# DualETH_CON.net
KiCad netlist of a schematic drawn in Altium Designer
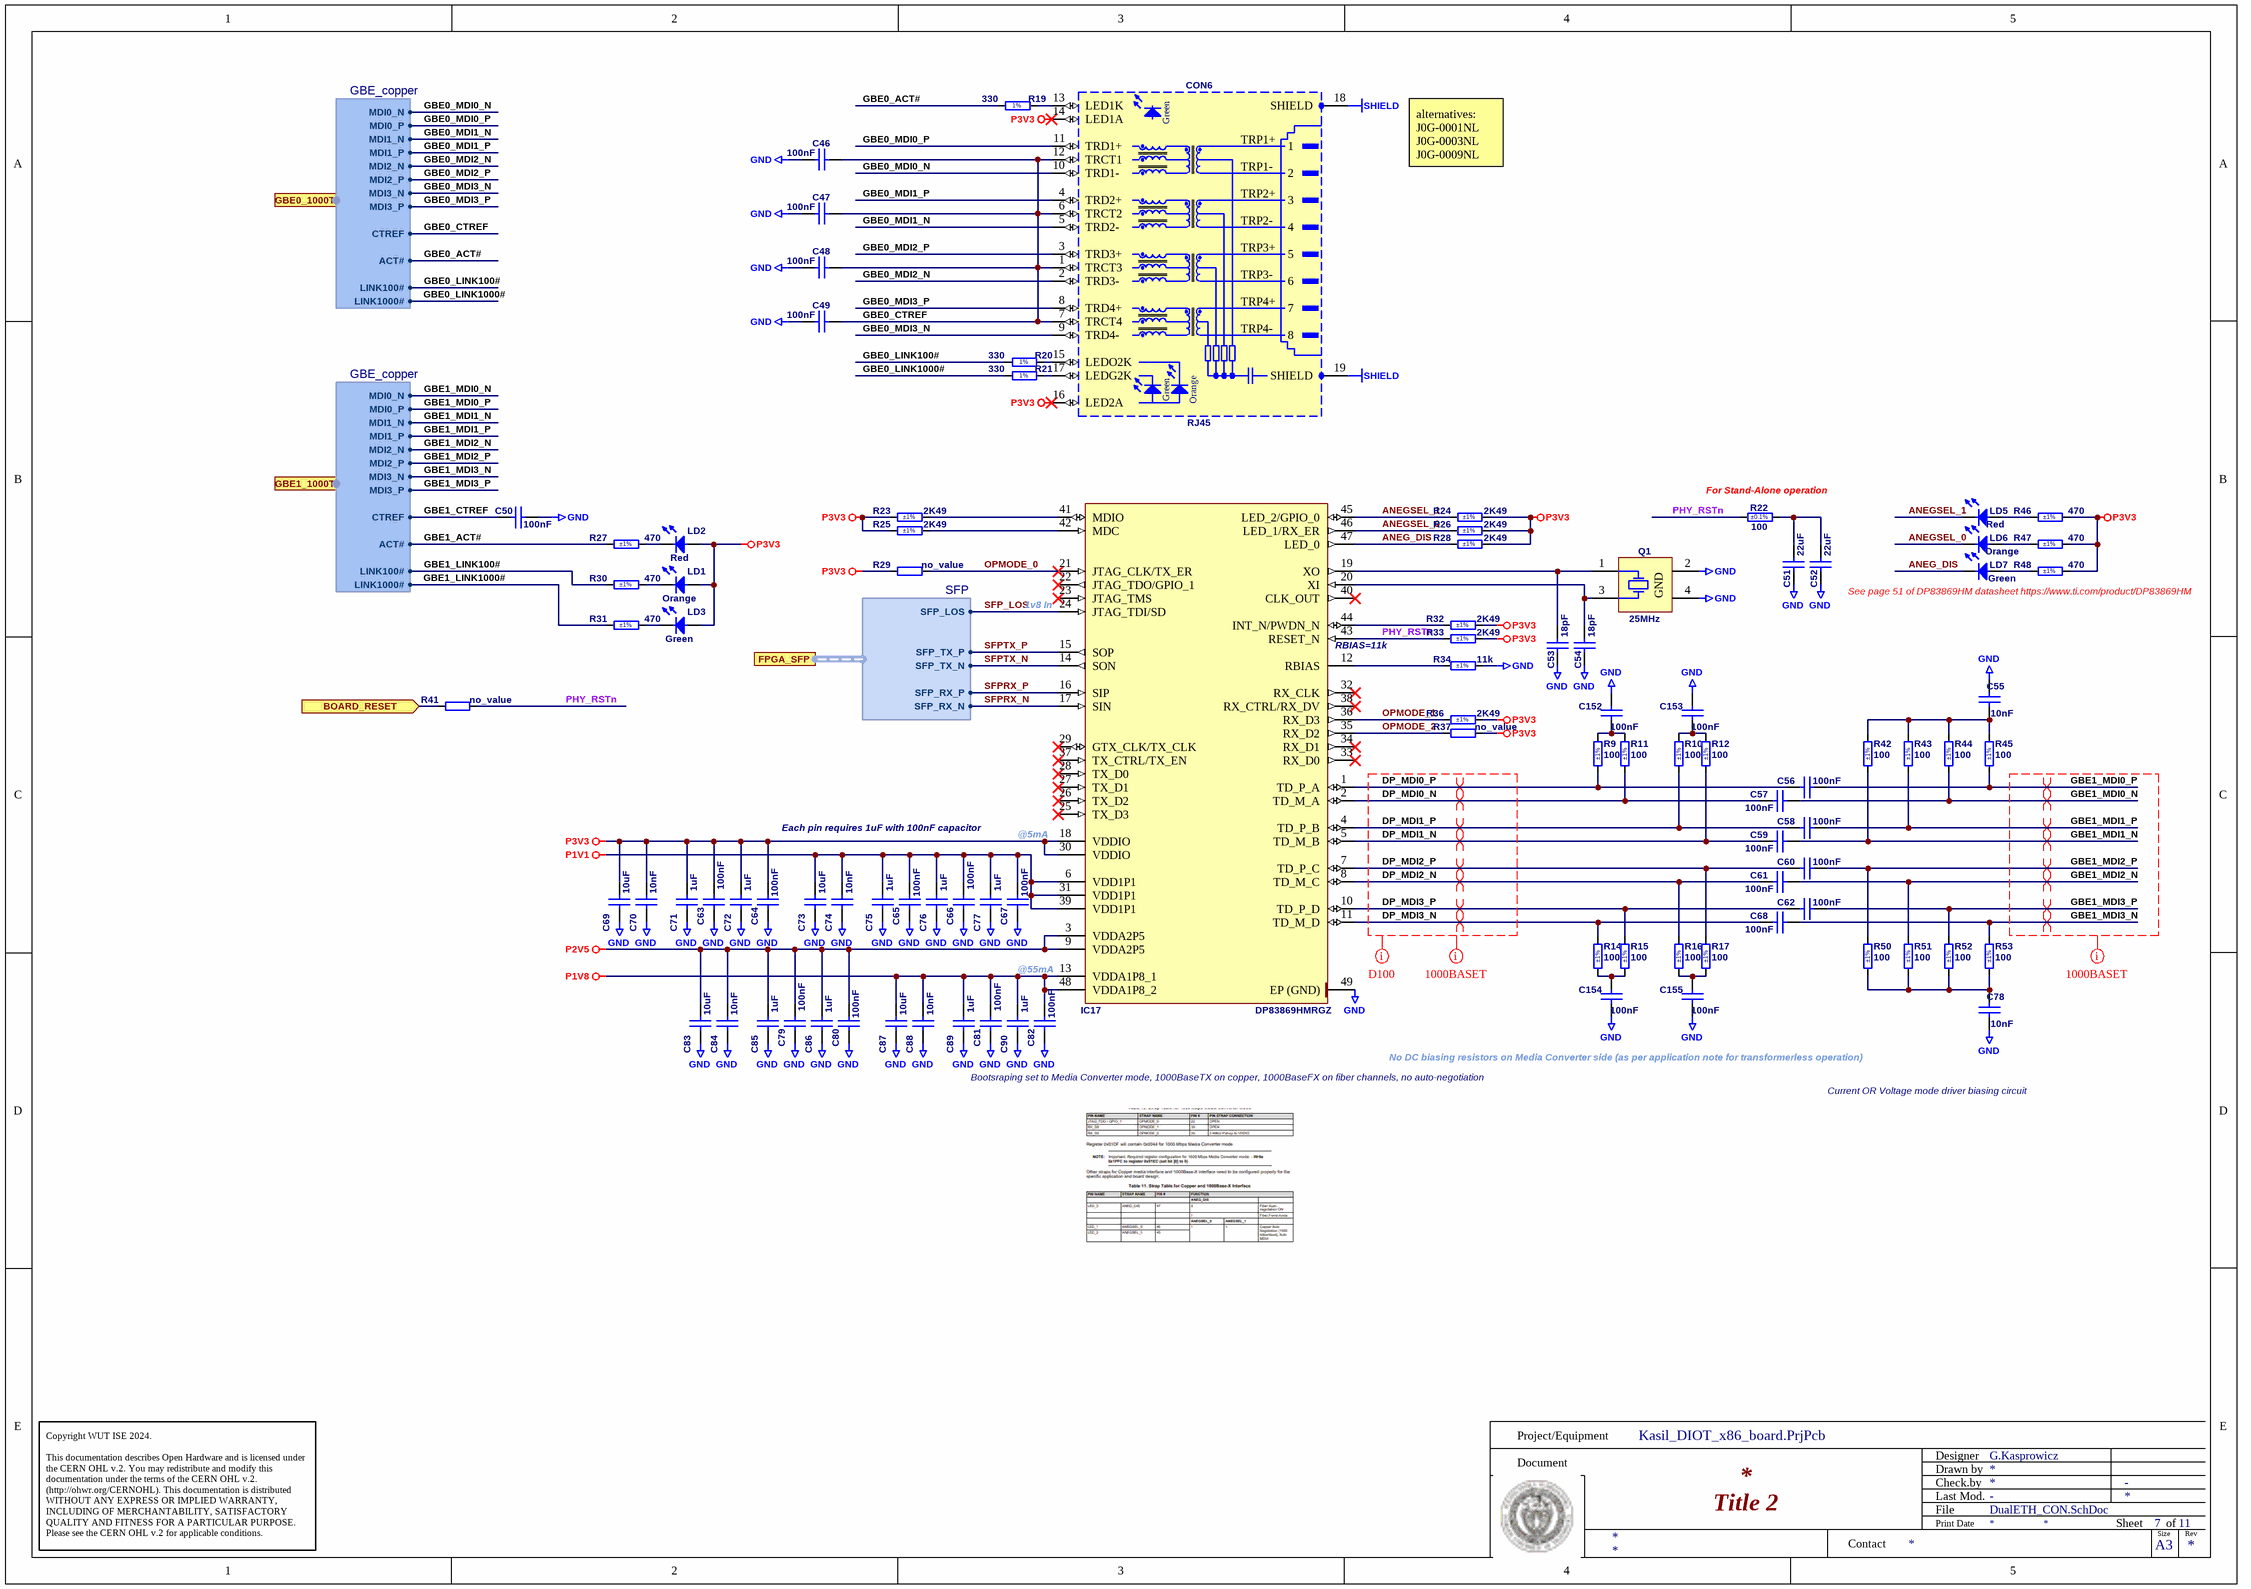
[diagram p0: DualETH_CON.SchDoc]

(export (version "E")
  (design (tool "Eeschema 10.0.6"))
  (components
    (comp (ref "C46")
      (value "100nF")
      (footprint "CAPC1005X55N")
      (description "Non-polarised capacitor")
      (fields (field (name "PART NUMBER") "CC0402_100NF_16V_10%_X7R") (field (name "VOLTAGE") "16V"))
      (libsource (lib "Capacitors") (part "Capacitor - non polarized"))
    )
    (comp (ref "C47")
      (value "100nF")
      (footprint "CAPC1005X55N")
      (description "Non-polarised capacitor")
      (fields (field (name "PART NUMBER") "CC0402_100NF_16V_10%_X7R") (field (name "VOLTAGE") "16V"))
      (libsource (lib "Capacitors") (part "Capacitor - non polarized"))
    )
    (comp (ref "C48")
      (value "100nF")
      (footprint "CAPC1005X55N")
      (description "Non-polarised capacitor")
      (fields (field (name "PART NUMBER") "CC0402_100NF_16V_10%_X7R") (field (name "VOLTAGE") "16V"))
      (libsource (lib "Capacitors") (part "Capacitor - non polarized"))
    )
    (comp (ref "C49")
      (value "100nF")
      (footprint "CAPC1005X55N")
      (description "Non-polarised capacitor")
      (fields (field (name "PART NUMBER") "CC0402_100NF_16V_10%_X7R") (field (name "VOLTAGE") "16V"))
      (libsource (lib "Capacitors") (part "Capacitor - non polarized"))
    )
    (comp (ref "C50")
      (value "100nF")
      (footprint "CAPC1005X55N")
      (description "Non-polarised capacitor")
      (fields (field (name "PART NUMBER") "CC0402_100NF_16V_10%_X7R") (field (name "VOLTAGE") "16V"))
      (libsource (lib "Capacitors") (part "Capacitor - non polarized"))
    )
    (comp (ref "C51")
      (value "22uF")
      (footprint "CAPC2012X135N")
      (description "Non-polarised capacitor")
      (fields
        (field (name "MANUFACTURER PART NUMBER") "CC0805_22UF_16V_10%_X5R")
        (field (name "MANUFACTURER") "GENERIC")
      )
      (libsource (lib "Capacitors") (part "Capacitor - non polarized"))
    )
    (comp (ref "C52")
      (value "22uF")
      (footprint "CAPC2012X135N")
      (description "Non-polarised capacitor")
      (fields
        (field (name "MANUFACTURER PART NUMBER") "CC0805_22UF_16V_10%_X5R")
        (field (name "MANUFACTURER") "GENERIC")
      )
      (libsource (lib "Capacitors") (part "Capacitor - non polarized"))
    )
    (comp (ref "C53")
      (value "18pF")
      (footprint "CAPC1005X55N")
      (description "Non-polarised capacitor")
      (fields (field (name "PART NUMBER") "CC0402_18PF_50V_5%_C0G") (field (name "VOLTAGE") "50V"))
      (libsource (lib "Capacitors") (part "Capacitor - non polarized"))
    )
    (comp (ref "C54")
      (value "18pF")
      (footprint "CAPC1005X55N")
      (description "Non-polarised capacitor")
      (fields (field (name "PART NUMBER") "CC0402_18PF_50V_5%_C0G") (field (name "VOLTAGE") "50V"))
      (libsource (lib "Capacitors") (part "Capacitor - non polarized"))
    )
    (comp (ref "C55")
      (value "10nF")
      (footprint "CAPC1005X55N")
      (description "Non-polarised capacitor")
      (fields (field (name "PART NUMBER") "CC0402_10NF_16V_10%_X7R") (field (name "VOLTAGE") "16V"))
      (libsource (lib "Capacitors") (part "Capacitor - non polarized"))
    )
    (comp (ref "C56")
      (value "100nF")
      (footprint "CAPC1005X55N")
      (description "Non-polarised capacitor")
      (fields (field (name "PART NUMBER") "CC0402_100NF_16V_10%_X7R") (field (name "VOLTAGE") "16V"))
      (libsource (lib "Capacitors") (part "Capacitor - non polarized"))
    )
    (comp (ref "C57")
      (value "100nF")
      (footprint "CAPC1005X55N")
      (description "Non-polarised capacitor")
      (fields (field (name "PART NUMBER") "CC0402_100NF_16V_10%_X7R") (field (name "VOLTAGE") "16V"))
      (libsource (lib "Capacitors") (part "Capacitor - non polarized"))
    )
    (comp (ref "C58")
      (value "100nF")
      (footprint "CAPC1005X55N")
      (description "Non-polarised capacitor")
      (fields (field (name "PART NUMBER") "CC0402_100NF_16V_10%_X7R") (field (name "VOLTAGE") "16V"))
      (libsource (lib "Capacitors") (part "Capacitor - non polarized"))
    )
    (comp (ref "C59")
      (value "100nF")
      (footprint "CAPC1005X55N")
      (description "Non-polarised capacitor")
      (fields (field (name "PART NUMBER") "CC0402_100NF_16V_10%_X7R") (field (name "VOLTAGE") "16V"))
      (libsource (lib "Capacitors") (part "Capacitor - non polarized"))
    )
    (comp (ref "C60")
      (value "100nF")
      (footprint "CAPC1005X55N")
      (description "Non-polarised capacitor")
      (fields (field (name "PART NUMBER") "CC0402_100NF_16V_10%_X7R") (field (name "VOLTAGE") "16V"))
      (libsource (lib "Capacitors") (part "Capacitor - non polarized"))
    )
    (comp (ref "C61")
      (value "100nF")
      (footprint "CAPC1005X55N")
      (description "Non-polarised capacitor")
      (fields (field (name "PART NUMBER") "CC0402_100NF_16V_10%_X7R") (field (name "VOLTAGE") "16V"))
      (libsource (lib "Capacitors") (part "Capacitor - non polarized"))
    )
    (comp (ref "C62")
      (value "100nF")
      (footprint "CAPC1005X55N")
      (description "Non-polarised capacitor")
      (fields (field (name "PART NUMBER") "CC0402_100NF_16V_10%_X7R") (field (name "VOLTAGE") "16V"))
      (libsource (lib "Capacitors") (part "Capacitor - non polarized"))
    )
    (comp (ref "C63")
      (value "100nF")
      (footprint "CAPC1005X55N")
      (description "Non-polarised capacitor")
      (fields (field (name "PART NUMBER") "CC0402_100NF_16V_10%_X7R") (field (name "VOLTAGE") "16V"))
      (libsource (lib "Capacitors") (part "Capacitor - non polarized"))
    )
    (comp (ref "C64")
      (value "100nF")
      (footprint "CAPC1005X55N")
      (description "Non-polarised capacitor")
      (fields (field (name "PART NUMBER") "CC0402_100NF_16V_10%_X7R") (field (name "VOLTAGE") "16V"))
      (libsource (lib "Capacitors") (part "Capacitor - non polarized"))
    )
    (comp (ref "C65")
      (value "100nF")
      (footprint "CAPC1005X55N")
      (description "Non-polarised capacitor")
      (fields (field (name "PART NUMBER") "CC0402_100NF_16V_10%_X7R") (field (name "VOLTAGE") "16V"))
      (libsource (lib "Capacitors") (part "Capacitor - non polarized"))
    )
    (comp (ref "C66")
      (value "100nF")
      (footprint "CAPC1005X55N")
      (description "Non-polarised capacitor")
      (fields (field (name "PART NUMBER") "CC0402_100NF_16V_10%_X7R") (field (name "VOLTAGE") "16V"))
      (libsource (lib "Capacitors") (part "Capacitor - non polarized"))
    )
    (comp (ref "C67")
      (value "100nF")
      (footprint "CAPC1005X55N")
      (description "Non-polarised capacitor")
      (fields (field (name "PART NUMBER") "CC0402_100NF_16V_10%_X7R") (field (name "VOLTAGE") "16V"))
      (libsource (lib "Capacitors") (part "Capacitor - non polarized"))
    )
    (comp (ref "C68")
      (value "100nF")
      (footprint "CAPC1005X55N")
      (description "Non-polarised capacitor")
      (fields (field (name "PART NUMBER") "CC0402_100NF_16V_10%_X7R") (field (name "VOLTAGE") "16V"))
      (libsource (lib "Capacitors") (part "Capacitor - non polarized"))
    )
    (comp (ref "C69")
      (value "10uF")
      (footprint "CAPC1608X80N")
      (description "Non-polarised capacitor")
      (fields (field (name "PART NUMBER") "CC0603_10UF_16V_20%_X5R") (field (name "VOLTAGE") "16V"))
      (libsource (lib "Capacitors") (part "Capacitor - non polarized"))
    )
    (comp (ref "C70")
      (value "10nF")
      (footprint "CAPC1005X55N")
      (description "Non-polarised capacitor")
      (fields (field (name "PART NUMBER") "CC0402_10NF_16V_10%_X7R") (field (name "VOLTAGE") "16V"))
      (libsource (lib "Capacitors") (part "Capacitor - non polarized"))
    )
    (comp (ref "C71")
      (value "1uF")
      (footprint "CAPC1005X55N")
      (description "Non-polarised capacitor")
      (fields (field (name "PART NUMBER") "CC0402_1UF_16V_10%_X5R") (field (name "VOLTAGE") "16V"))
      (libsource (lib "Capacitors") (part "Capacitor - non polarized"))
    )
    (comp (ref "C72")
      (value "1uF")
      (footprint "CAPC1005X55N")
      (description "Non-polarised capacitor")
      (fields (field (name "PART NUMBER") "CC0402_1UF_16V_10%_X5R") (field (name "VOLTAGE") "16V"))
      (libsource (lib "Capacitors") (part "Capacitor - non polarized"))
    )
    (comp (ref "C73")
      (value "10uF")
      (footprint "CAPC1608X80N")
      (description "Non-polarised capacitor")
      (fields (field (name "PART NUMBER") "CC0603_10UF_16V_20%_X5R") (field (name "VOLTAGE") "16V"))
      (libsource (lib "Capacitors") (part "Capacitor - non polarized"))
    )
    (comp (ref "C74")
      (value "10nF")
      (footprint "CAPC1005X55N")
      (description "Non-polarised capacitor")
      (fields (field (name "PART NUMBER") "CC0402_10NF_16V_10%_X7R") (field (name "VOLTAGE") "16V"))
      (libsource (lib "Capacitors") (part "Capacitor - non polarized"))
    )
    (comp (ref "C75")
      (value "1uF")
      (footprint "CAPC1005X55N")
      (description "Non-polarised capacitor")
      (fields (field (name "PART NUMBER") "CC0402_1UF_16V_10%_X5R") (field (name "VOLTAGE") "16V"))
      (libsource (lib "Capacitors") (part "Capacitor - non polarized"))
    )
    (comp (ref "C76")
      (value "1uF")
      (footprint "CAPC1005X55N")
      (description "Non-polarised capacitor")
      (fields (field (name "PART NUMBER") "CC0402_1UF_16V_10%_X5R") (field (name "VOLTAGE") "16V"))
      (libsource (lib "Capacitors") (part "Capacitor - non polarized"))
    )
    (comp (ref "C77")
      (value "1uF")
      (footprint "CAPC1005X55N")
      (description "Non-polarised capacitor")
      (fields (field (name "PART NUMBER") "CC0402_1UF_16V_10%_X5R") (field (name "VOLTAGE") "16V"))
      (libsource (lib "Capacitors") (part "Capacitor - non polarized"))
    )
    (comp (ref "C78")
      (value "10nF")
      (footprint "CAPC1005X55N")
      (description "Non-polarised capacitor")
      (fields (field (name "PART NUMBER") "CC0402_10NF_16V_10%_X7R") (field (name "VOLTAGE") "16V"))
      (libsource (lib "Capacitors") (part "Capacitor - non polarized"))
    )
    (comp (ref "C79")
      (value "100nF")
      (footprint "CAPC1005X55N")
      (description "Non-polarised capacitor")
      (fields (field (name "PART NUMBER") "CC0402_100NF_16V_10%_X7R") (field (name "VOLTAGE") "16V"))
      (libsource (lib "Capacitors") (part "Capacitor - non polarized"))
    )
    (comp (ref "C80")
      (value "100nF")
      (footprint "CAPC1005X55N")
      (description "Non-polarised capacitor")
      (fields (field (name "PART NUMBER") "CC0402_100NF_16V_10%_X7R") (field (name "VOLTAGE") "16V"))
      (libsource (lib "Capacitors") (part "Capacitor - non polarized"))
    )
    (comp (ref "C81")
      (value "100nF")
      (footprint "CAPC1005X55N")
      (description "Non-polarised capacitor")
      (fields (field (name "PART NUMBER") "CC0402_100NF_16V_10%_X7R") (field (name "VOLTAGE") "16V"))
      (libsource (lib "Capacitors") (part "Capacitor - non polarized"))
    )
    (comp (ref "C82")
      (value "100nF")
      (footprint "CAPC1005X55N")
      (description "Non-polarised capacitor")
      (fields (field (name "PART NUMBER") "CC0402_100NF_16V_10%_X7R") (field (name "VOLTAGE") "16V"))
      (libsource (lib "Capacitors") (part "Capacitor - non polarized"))
    )
    (comp (ref "C83")
      (value "10uF")
      (footprint "CAPC1608X80N")
      (description "Non-polarised capacitor")
      (fields (field (name "PART NUMBER") "CC0603_10UF_16V_20%_X5R") (field (name "VOLTAGE") "16V"))
      (libsource (lib "Capacitors") (part "Capacitor - non polarized"))
    )
    (comp (ref "C84")
      (value "10nF")
      (footprint "CAPC1005X55N")
      (description "Non-polarised capacitor")
      (fields (field (name "PART NUMBER") "CC0402_10NF_16V_10%_X7R") (field (name "VOLTAGE") "16V"))
      (libsource (lib "Capacitors") (part "Capacitor - non polarized"))
    )
    (comp (ref "C85")
      (value "1uF")
      (footprint "CAPC1005X55N")
      (description "Non-polarised capacitor")
      (fields (field (name "PART NUMBER") "CC0402_1UF_16V_10%_X5R") (field (name "VOLTAGE") "16V"))
      (libsource (lib "Capacitors") (part "Capacitor - non polarized"))
    )
    (comp (ref "C86")
      (value "1uF")
      (footprint "CAPC1005X55N")
      (description "Non-polarised capacitor")
      (fields (field (name "PART NUMBER") "CC0402_1UF_16V_10%_X5R") (field (name "VOLTAGE") "16V"))
      (libsource (lib "Capacitors") (part "Capacitor - non polarized"))
    )
    (comp (ref "C87")
      (value "10uF")
      (footprint "CAPC1608X80N")
      (description "Non-polarised capacitor")
      (fields (field (name "PART NUMBER") "CC0603_10UF_16V_20%_X5R") (field (name "VOLTAGE") "16V"))
      (libsource (lib "Capacitors") (part "Capacitor - non polarized"))
    )
    (comp (ref "C88")
      (value "10nF")
      (footprint "CAPC1005X55N")
      (description "Non-polarised capacitor")
      (fields (field (name "PART NUMBER") "CC0402_10NF_16V_10%_X7R") (field (name "VOLTAGE") "16V"))
      (libsource (lib "Capacitors") (part "Capacitor - non polarized"))
    )
    (comp (ref "C89")
      (value "1uF")
      (footprint "CAPC1005X55N")
      (description "Non-polarised capacitor")
      (fields (field (name "PART NUMBER") "CC0402_1UF_16V_10%_X5R") (field (name "VOLTAGE") "16V"))
      (libsource (lib "Capacitors") (part "Capacitor - non polarized"))
    )
    (comp (ref "C90")
      (value "1uF")
      (footprint "CAPC1005X55N")
      (description "Non-polarised capacitor")
      (fields (field (name "PART NUMBER") "CC0402_1UF_16V_10%_X5R") (field (name "VOLTAGE") "16V"))
      (libsource (lib "Capacitors") (part "Capacitor - non polarized"))
    )
    (comp (ref "C152")
      (value "100nF")
      (footprint "CAPC1005X55N")
      (description "Non-polarised capacitor")
      (fields (field (name "PART NUMBER") "CC0402_100NF_16V_10%_X7R") (field (name "VOLTAGE") "16V"))
      (libsource (lib "Capacitors") (part "Capacitor - non polarized"))
    )
    (comp (ref "C153")
      (value "100nF")
      (footprint "CAPC1005X55N")
      (description "Non-polarised capacitor")
      (fields (field (name "PART NUMBER") "CC0402_100NF_16V_10%_X7R") (field (name "VOLTAGE") "16V"))
      (libsource (lib "Capacitors") (part "Capacitor - non polarized"))
    )
    (comp (ref "C154")
      (value "100nF")
      (footprint "CAPC1005X55N")
      (description "Non-polarised capacitor")
      (fields (field (name "PART NUMBER") "CC0402_100NF_16V_10%_X7R") (field (name "VOLTAGE") "16V"))
      (libsource (lib "Capacitors") (part "Capacitor - non polarized"))
    )
    (comp (ref "C155")
      (value "100nF")
      (footprint "CAPC1005X55N")
      (description "Non-polarised capacitor")
      (fields (field (name "PART NUMBER") "CC0402_100NF_16V_10%_X7R") (field (name "VOLTAGE") "16V"))
      (libsource (lib "Capacitors") (part "Capacitor - non polarized"))
    )
    (comp (ref "CON6")
      (value "RJ45")
      (footprint "BELFUSE_L829-1J1T-43")
      (description "1 Port, RJ45, Gigabit Ethernet, MagJack Connector Module With Yellow And Green/Orange LEDs,")
      (fields (field (name "PART NUMBER") "BELFUSE_L829-1J1T-43") (field (name "MANUFACTURER") "BELFUSE"))
      (libsource (lib "Connectors") (part "BELFUSE_L829-1J1T-43"))
    )
    (comp (ref "IC17")
      (value "DP83869HMRGZ")
      (footprint "QFN50P700X700X100-49N-S420")
      (fields (field (name "MANUFACTURER") "TEXAS INSTRUMENTS"))
      (libsource (lib "ICs And Semiconductors") (part "DP83869HMRGZ"))
    )
    (comp (ref "LD1")
      (value "Orange")
      (footprint "LED_DIALIGHT_597-2111-407F")
      (fields
        (field (name "PART NUMBER") "LED_DIALIGHT_597-2111-407F")
        (field (name "MANUFACTURER") "DIALIGHT")
        (field (name "MANUFACTURER PART NUMBER") "597-2111-407F")
      )
      (libsource (lib "ICs And Semiconductors") (part "LED Red 1C 2A"))
    )
    (comp (ref "LD2")
      (value "Red")
      (footprint "LED_DIALIGHT_597-2111-407F")
      (fields
        (field (name "PART NUMBER") "LED_DIALIGHT_597-2111-407F")
        (field (name "MANUFACTURER") "DIALIGHT")
        (field (name "MANUFACTURER PART NUMBER") "597-2111-407F")
      )
      (libsource (lib "ICs And Semiconductors") (part "LED Red 1C 2A"))
    )
    (comp (ref "LD3")
      (value "Green")
      (footprint "LED_DIALIGHT_597-2111-407F")
      (fields
        (field (name "PART NUMBER") "LED_DIALIGHT_597-2111-407F")
        (field (name "MANUFACTURER") "DIALIGHT")
        (field (name "MANUFACTURER PART NUMBER") "597-2111-407F")
      )
      (libsource (lib "ICs And Semiconductors") (part "LED Red 1C 2A"))
    )
    (comp (ref "LD5")
      (value "Red")
      (footprint "LED_DIALIGHT_597-2111-407F")
      (fields
        (field (name "PART NUMBER") "LED_DIALIGHT_597-2111-407F")
        (field (name "MANUFACTURER") "DIALIGHT")
        (field (name "MANUFACTURER PART NUMBER") "597-2111-407F")
      )
      (libsource (lib "ICs And Semiconductors") (part "LED Red 1C 2A"))
    )
    (comp (ref "LD6")
      (value "Orange")
      (footprint "LED_DIALIGHT_597-2111-407F")
      (fields
        (field (name "PART NUMBER") "LED_DIALIGHT_597-2111-407F")
        (field (name "MANUFACTURER") "DIALIGHT")
        (field (name "MANUFACTURER PART NUMBER") "597-2111-407F")
      )
      (libsource (lib "ICs And Semiconductors") (part "LED Red 1C 2A"))
    )
    (comp (ref "LD7")
      (value "Green")
      (footprint "LED_DIALIGHT_597-2111-407F")
      (fields
        (field (name "PART NUMBER") "LED_DIALIGHT_597-2111-407F")
        (field (name "MANUFACTURER") "DIALIGHT")
        (field (name "MANUFACTURER PART NUMBER") "597-2111-407F")
      )
      (libsource (lib "ICs And Semiconductors") (part "LED Red 1C 2A"))
    )
    (comp (ref "Q1")
      (value "25MHz")
      (footprint "XTAL_EPSON_TSX-3225")
      (description "Crystal 4 pins 1=XTAL Control 2=GND3=XTAL 4=GND")
      (fields
        (field (name "PART NUMBER") "XTAL_25MHZ_EPSON_TSX-3225 25.0000MF10Z-AC")
        (field (name "MANUFACTURER") "EPSON")
      )
      (libsource (lib "ICs And Semiconductors") (part "Quartz Crystal 1X 2GND 3X 4GND"))
    )
    (comp (ref "R9")
      (value "100")
      (footprint "RESC1005X40N")
      (description "Resistor - 1%")
      (fields
        (field (name "TOLERANCE") "±1%")
        (field (name "PART NUMBER") "R0402_100R_1%_0.0625W_100PPM")
        (field (name "POWER") "0.0625W")
      )
      (libsource (lib "Resistors") (part "Resistor - 1%"))
    )
    (comp (ref "R10")
      (value "100")
      (footprint "RESC1005X40N")
      (description "Resistor - 1%")
      (fields
        (field (name "TOLERANCE") "±1%")
        (field (name "PART NUMBER") "R0402_100R_1%_0.0625W_100PPM")
        (field (name "POWER") "0.0625W")
      )
      (libsource (lib "Resistors") (part "Resistor - 1%"))
    )
    (comp (ref "R11")
      (value "100")
      (footprint "RESC1005X40N")
      (description "Resistor - 1%")
      (fields
        (field (name "TOLERANCE") "±1%")
        (field (name "PART NUMBER") "R0402_100R_1%_0.0625W_100PPM")
        (field (name "POWER") "0.0625W")
      )
      (libsource (lib "Resistors") (part "Resistor - 1%"))
    )
    (comp (ref "R12")
      (value "100")
      (footprint "RESC1005X40N")
      (description "Resistor - 1%")
      (fields
        (field (name "TOLERANCE") "±1%")
        (field (name "PART NUMBER") "R0402_100R_1%_0.0625W_100PPM")
        (field (name "POWER") "0.0625W")
      )
      (libsource (lib "Resistors") (part "Resistor - 1%"))
    )
    (comp (ref "R14")
      (value "100")
      (footprint "RESC1005X40N")
      (description "Resistor - 1%")
      (fields
        (field (name "TOLERANCE") "±1%")
        (field (name "PART NUMBER") "R0402_100R_1%_0.0625W_100PPM")
        (field (name "POWER") "0.0625W")
      )
      (libsource (lib "Resistors") (part "Resistor - 1%"))
    )
    (comp (ref "R15")
      (value "100")
      (footprint "RESC1005X40N")
      (description "Resistor - 1%")
      (fields
        (field (name "TOLERANCE") "±1%")
        (field (name "PART NUMBER") "R0402_100R_1%_0.0625W_100PPM")
        (field (name "POWER") "0.0625W")
      )
      (libsource (lib "Resistors") (part "Resistor - 1%"))
    )
    (comp (ref "R16")
      (value "100")
      (footprint "RESC1005X40N")
      (description "Resistor - 1%")
      (fields
        (field (name "TOLERANCE") "±1%")
        (field (name "PART NUMBER") "R0402_100R_1%_0.0625W_100PPM")
        (field (name "POWER") "0.0625W")
      )
      (libsource (lib "Resistors") (part "Resistor - 1%"))
    )
    (comp (ref "R17")
      (value "100")
      (footprint "RESC1005X40N")
      (description "Resistor - 1%")
      (fields
        (field (name "TOLERANCE") "±1%")
        (field (name "PART NUMBER") "R0402_100R_1%_0.0625W_100PPM")
        (field (name "POWER") "0.0625W")
      )
      (libsource (lib "Resistors") (part "Resistor - 1%"))
    )
    (comp (ref "R19")
      (value "330")
      (footprint "RESC1608X55N")
      (description "Resistor - 1%")
      (fields (field (name "PART NUMBER") "R0603_330R_1%_0.1W_100PPM") (field (name "POWER") "0.1W"))
      (libsource (lib "") (part "Resistor - 1%_1"))
    )
    (comp (ref "R20")
      (value "330")
      (footprint "RESC1608X55N")
      (description "Resistor - 1%")
      (fields (field (name "PART NUMBER") "R0603_330R_1%_0.1W_100PPM") (field (name "POWER") "0.1W"))
      (libsource (lib "") (part "Resistor - 1%_1"))
    )
    (comp (ref "R21")
      (value "330")
      (footprint "RESC1608X55N")
      (description "Resistor - 1%")
      (fields (field (name "PART NUMBER") "R0603_330R_1%_0.1W_100PPM") (field (name "POWER") "0.1W"))
      (libsource (lib "") (part "Resistor - 1%_1"))
    )
    (comp (ref "R22")
      (value "100")
      (footprint "RESC1005X35N")
      (description "Resistor - 0.1%")
      (fields
        (field (name "TOLERANCE") "±0.1%")
        (field (name "PART NUMBER") "R0402_100R_0.1%_0.063W_25PPM")
        (field (name "POWER") "0.063W")
      )
      (libsource (lib "Resistors") (part "Resistor - 0.1%"))
    )
    (comp (ref "R23")
      (value "2K49")
      (footprint "RESC1005X40N")
      (description "Resistor - 1%")
      (fields
        (field (name "TOLERANCE") "±1%")
        (field (name "PART NUMBER") "R0402_2K49_1%_0.063W_100PPM")
        (field (name "POWER") "0.063W")
      )
      (libsource (lib "Resistors") (part "Resistor - 1%"))
    )
    (comp (ref "R24")
      (value "2K49")
      (footprint "RESC1005X40N")
      (description "Resistor - 1%")
      (fields
        (field (name "TOLERANCE") "±1%")
        (field (name "PART NUMBER") "R0402_2K49_1%_0.063W_100PPM")
        (field (name "POWER") "0.063W")
      )
      (libsource (lib "Resistors") (part "Resistor - 1%"))
    )
    (comp (ref "R25")
      (value "2K49")
      (footprint "RESC1005X40N")
      (description "Resistor - 1%")
      (fields
        (field (name "TOLERANCE") "±1%")
        (field (name "PART NUMBER") "R0402_2K49_1%_0.063W_100PPM")
        (field (name "POWER") "0.063W")
      )
      (libsource (lib "Resistors") (part "Resistor - 1%"))
    )
    (comp (ref "R26")
      (value "2K49")
      (footprint "RESC1005X40N")
      (description "Resistor - 1%")
      (fields
        (field (name "TOLERANCE") "±1%")
        (field (name "PART NUMBER") "R0402_2K49_1%_0.063W_100PPM")
        (field (name "POWER") "0.063W")
      )
      (libsource (lib "Resistors") (part "Resistor - 1%"))
    )
    (comp (ref "R27")
      (value "470")
      (footprint "RESC1005X40N")
      (description "Resistor - 1%")
      (fields
        (field (name "TOLERANCE") "±1%")
        (field (name "PART NUMBER") "R0402_470R_1%_0.0625W_100PPM")
        (field (name "POWER") "0.0625W")
      )
      (libsource (lib "Resistors") (part "Resistor - 1%"))
    )
    (comp (ref "R28")
      (value "2K49")
      (footprint "RESC1005X40N")
      (description "Resistor - 1%")
      (fields
        (field (name "TOLERANCE") "±1%")
        (field (name "PART NUMBER") "R0402_2K49_1%_0.063W_100PPM")
        (field (name "POWER") "0.063W")
      )
      (libsource (lib "Resistors") (part "Resistor - 1%"))
    )
    (comp (ref "R29")
      (value "no_value")
      (footprint "RESC1005X40N")
      (description "Resistor")
      (fields (field (name "PART NUMBER") "R0402_0R_JUMPER") (field (name "MANUFACTURER") "GENERIC"))
      (libsource (lib "Resistors") (part "Resistor"))
    )
    (comp (ref "R30")
      (value "470")
      (footprint "RESC1005X40N")
      (description "Resistor - 1%")
      (fields
        (field (name "TOLERANCE") "±1%")
        (field (name "PART NUMBER") "R0402_470R_1%_0.0625W_100PPM")
        (field (name "POWER") "0.0625W")
      )
      (libsource (lib "Resistors") (part "Resistor - 1%"))
    )
    (comp (ref "R31")
      (value "470")
      (footprint "RESC1005X40N")
      (description "Resistor - 1%")
      (fields
        (field (name "TOLERANCE") "±1%")
        (field (name "PART NUMBER") "R0402_470R_1%_0.0625W_100PPM")
        (field (name "POWER") "0.0625W")
      )
      (libsource (lib "Resistors") (part "Resistor - 1%"))
    )
    (comp (ref "R32")
      (value "2K49")
      (footprint "RESC1005X40N")
      (description "Resistor - 1%")
      (fields
        (field (name "TOLERANCE") "±1%")
        (field (name "PART NUMBER") "R0402_2K49_1%_0.063W_100PPM")
        (field (name "POWER") "0.063W")
      )
      (libsource (lib "Resistors") (part "Resistor - 1%"))
    )
    (comp (ref "R33")
      (value "2K49")
      (footprint "RESC1005X40N")
      (description "Resistor - 1%")
      (fields
        (field (name "TOLERANCE") "±1%")
        (field (name "PART NUMBER") "R0402_2K49_1%_0.063W_100PPM")
        (field (name "POWER") "0.063W")
      )
      (libsource (lib "Resistors") (part "Resistor - 1%"))
    )
    (comp (ref "R34")
      (value "11k")
      (footprint "RESC1005X40N")
      (description "Resistor - 1%")
      (fields
        (field (name "TOLERANCE") "±1%")
        (field (name "PART NUMBER") "R0402_11K_1%_0.0625W_100PPM")
        (field (name "POWER") "0.0625W")
      )
      (libsource (lib "Resistors") (part "Resistor - 1%"))
    )
    (comp (ref "R36")
      (value "2K49")
      (footprint "RESC1005X40N")
      (description "Resistor - 1%")
      (fields
        (field (name "TOLERANCE") "±1%")
        (field (name "PART NUMBER") "R0402_2K49_1%_0.063W_100PPM")
        (field (name "POWER") "0.063W")
      )
      (libsource (lib "Resistors") (part "Resistor - 1%"))
    )
    (comp (ref "R37")
      (value "no_value")
      (footprint "RESC1005X40N")
      (description "Resistor")
      (fields (field (name "PART NUMBER") "R0402_0R_JUMPER") (field (name "MANUFACTURER") "GENERIC"))
      (libsource (lib "Resistors") (part "Resistor"))
    )
    (comp (ref "R41")
      (value "no_value")
      (footprint "RESC1005X40N")
      (description "Resistor")
      (fields (field (name "PART NUMBER") "R0402_0R_JUMPER") (field (name "MANUFACTURER") "GENERIC"))
      (libsource (lib "Resistors") (part "Resistor"))
    )
    (comp (ref "R42")
      (value "100")
      (footprint "RESC1005X40N")
      (description "Resistor - 1%")
      (fields
        (field (name "TOLERANCE") "±1%")
        (field (name "PART NUMBER") "R0402_100R_1%_0.0625W_100PPM")
        (field (name "POWER") "0.0625W")
      )
      (libsource (lib "Resistors") (part "Resistor - 1%"))
    )
    (comp (ref "R43")
      (value "100")
      (footprint "RESC1005X40N")
      (description "Resistor - 1%")
      (fields
        (field (name "TOLERANCE") "±1%")
        (field (name "PART NUMBER") "R0402_100R_1%_0.0625W_100PPM")
        (field (name "POWER") "0.0625W")
      )
      (libsource (lib "Resistors") (part "Resistor - 1%"))
    )
    (comp (ref "R44")
      (value "100")
      (footprint "RESC1005X40N")
      (description "Resistor - 1%")
      (fields
        (field (name "TOLERANCE") "±1%")
        (field (name "PART NUMBER") "R0402_100R_1%_0.0625W_100PPM")
        (field (name "POWER") "0.0625W")
      )
      (libsource (lib "Resistors") (part "Resistor - 1%"))
    )
    (comp (ref "R45")
      (value "100")
      (footprint "RESC1005X40N")
      (description "Resistor - 1%")
      (fields
        (field (name "TOLERANCE") "±1%")
        (field (name "PART NUMBER") "R0402_100R_1%_0.0625W_100PPM")
        (field (name "POWER") "0.0625W")
      )
      (libsource (lib "Resistors") (part "Resistor - 1%"))
    )
    (comp (ref "R46")
      (value "470")
      (footprint "RESC1005X40N")
      (description "Resistor - 1%")
      (fields
        (field (name "TOLERANCE") "±1%")
        (field (name "PART NUMBER") "R0402_470R_1%_0.0625W_100PPM")
        (field (name "POWER") "0.0625W")
      )
      (libsource (lib "Resistors") (part "Resistor - 1%"))
    )
    (comp (ref "R47")
      (value "470")
      (footprint "RESC1005X40N")
      (description "Resistor - 1%")
      (fields
        (field (name "TOLERANCE") "±1%")
        (field (name "PART NUMBER") "R0402_470R_1%_0.0625W_100PPM")
        (field (name "POWER") "0.0625W")
      )
      (libsource (lib "Resistors") (part "Resistor - 1%"))
    )
    (comp (ref "R48")
      (value "470")
      (footprint "RESC1005X40N")
      (description "Resistor - 1%")
      (fields
        (field (name "TOLERANCE") "±1%")
        (field (name "PART NUMBER") "R0402_470R_1%_0.0625W_100PPM")
        (field (name "POWER") "0.0625W")
      )
      (libsource (lib "Resistors") (part "Resistor - 1%"))
    )
    (comp (ref "R50")
      (value "100")
      (footprint "RESC1005X40N")
      (description "Resistor - 1%")
      (fields
        (field (name "TOLERANCE") "±1%")
        (field (name "PART NUMBER") "R0402_100R_1%_0.0625W_100PPM")
        (field (name "POWER") "0.0625W")
      )
      (libsource (lib "Resistors") (part "Resistor - 1%"))
    )
    (comp (ref "R51")
      (value "100")
      (footprint "RESC1005X40N")
      (description "Resistor - 1%")
      (fields
        (field (name "TOLERANCE") "±1%")
        (field (name "PART NUMBER") "R0402_100R_1%_0.0625W_100PPM")
        (field (name "POWER") "0.0625W")
      )
      (libsource (lib "Resistors") (part "Resistor - 1%"))
    )
    (comp (ref "R52")
      (value "100")
      (footprint "RESC1005X40N")
      (description "Resistor - 1%")
      (fields
        (field (name "TOLERANCE") "±1%")
        (field (name "PART NUMBER") "R0402_100R_1%_0.0625W_100PPM")
        (field (name "POWER") "0.0625W")
      )
      (libsource (lib "Resistors") (part "Resistor - 1%"))
    )
    (comp (ref "R53")
      (value "100")
      (footprint "RESC1005X40N")
      (description "Resistor - 1%")
      (fields
        (field (name "TOLERANCE") "±1%")
        (field (name "PART NUMBER") "R0402_100R_1%_0.0625W_100PPM")
        (field (name "POWER") "0.0625W")
      )
      (libsource (lib "Resistors") (part "Resistor - 1%"))
    )
  )
  (nets
    (net (code "3") (name "/ANEGSEL_0") (class "Default")
      (node (ref "IC17") (pin "46") (pinfunction "LED_1/RX_ER_46") (pintype "output"))
      (node (ref "LD6") (pin "1") (pinfunction "C_1") (pintype "passive"))
      (node (ref "R26") (pin "1") (pinfunction "1_1") (pintype "passive"))
    )
    (net (code "4") (name "/ANEGSEL_1") (class "Default")
      (node (ref "IC17") (pin "45") (pinfunction "LED_2/GPIO_0_45") (pintype "bidirectional"))
      (node (ref "LD5") (pin "1") (pinfunction "C_1") (pintype "passive"))
      (node (ref "R24") (pin "1") (pinfunction "1_1") (pintype "passive"))
    )
    (net (code "5") (name "/ANEG_DIS") (class "Default")
      (node (ref "IC17") (pin "47") (pinfunction "LED_0_47") (pintype "output"))
      (node (ref "LD7") (pin "1") (pinfunction "C_1") (pintype "passive"))
      (node (ref "R28") (pin "1") (pinfunction "1_1") (pintype "passive"))
    )
    (net (code "6") (name "/BOARD_RESET") (class "Default")
      (node (ref "R41") (pin "1") (pinfunction "1_1") (pintype "passive"))
    )
    (net (code "7") (name "/DP_MDI0_N") (class "Default")
      (node (ref "C57") (pin "1") (pinfunction "1_1") (pintype "passive"))
      (node (ref "IC17") (pin "2") (pinfunction "TD_M_A_2") (pintype "bidirectional"))
      (node (ref "R11") (pin "1") (pinfunction "1_1") (pintype "passive"))
    )
    (net (code "8") (name "/DP_MDI0_P") (class "Default")
      (node (ref "C56") (pin "1") (pinfunction "1_1") (pintype "passive"))
      (node (ref "IC17") (pin "1") (pinfunction "TD_P_A_1") (pintype "bidirectional"))
      (node (ref "R9") (pin "1") (pinfunction "1_1") (pintype "passive"))
    )
    (net (code "9") (name "/DP_MDI1_N") (class "Default")
      (node (ref "C59") (pin "1") (pinfunction "1_1") (pintype "passive"))
      (node (ref "IC17") (pin "5") (pinfunction "TD_M_B_5") (pintype "bidirectional"))
      (node (ref "R12") (pin "1") (pinfunction "1_1") (pintype "passive"))
    )
    (net (code "10") (name "/DP_MDI1_P") (class "Default")
      (node (ref "C58") (pin "1") (pinfunction "1_1") (pintype "passive"))
      (node (ref "IC17") (pin "4") (pinfunction "TD_P_B_4") (pintype "bidirectional"))
      (node (ref "R10") (pin "1") (pinfunction "1_1") (pintype "passive"))
    )
    (net (code "11") (name "/DP_MDI2_N") (class "Default")
      (node (ref "C61") (pin "1") (pinfunction "1_1") (pintype "passive"))
      (node (ref "IC17") (pin "8") (pinfunction "TD_M_C_8") (pintype "bidirectional"))
      (node (ref "R16") (pin "2") (pinfunction "2_2") (pintype "passive"))
    )
    (net (code "12") (name "/DP_MDI2_P") (class "Default")
      (node (ref "C60") (pin "1") (pinfunction "1_1") (pintype "passive"))
      (node (ref "IC17") (pin "7") (pinfunction "TD_P_C_7") (pintype "bidirectional"))
      (node (ref "R17") (pin "2") (pinfunction "2_2") (pintype "passive"))
    )
    (net (code "13") (name "/DP_MDI3_N") (class "Default")
      (node (ref "C68") (pin "1") (pinfunction "1_1") (pintype "passive"))
      (node (ref "IC17") (pin "11") (pinfunction "TD_M_D_11") (pintype "bidirectional"))
      (node (ref "R14") (pin "2") (pinfunction "2_2") (pintype "passive"))
    )
    (net (code "14") (name "/DP_MDI3_P") (class "Default")
      (node (ref "C62") (pin "1") (pinfunction "1_1") (pintype "passive"))
      (node (ref "IC17") (pin "10") (pinfunction "TD_P_D_10") (pintype "bidirectional"))
      (node (ref "R15") (pin "2") (pinfunction "2_2") (pintype "passive"))
    )
    (net (code "15") (name "/GBE0_ACT#") (class "Default")
      (node (ref "R19") (pin "1") (pinfunction "1_1") (pintype "passive"))
    )
    (net (code "16") (name "/GBE0_CTREF") (class "Default")
      (node (ref "C46") (pin "2") (pinfunction "2_2") (pintype "passive"))
      (node (ref "C47") (pin "2") (pinfunction "2_2") (pintype "passive"))
      (node (ref "C48") (pin "2") (pinfunction "2_2") (pintype "passive"))
      (node (ref "C49") (pin "2") (pinfunction "2_2") (pintype "passive"))
      (node (ref "CON6") (pin "1") (pinfunction "TRCT3_1") (pintype "bidirectional"))
      (node (ref "CON6") (pin "12") (pinfunction "TRCT1_12") (pintype "bidirectional"))
      (node (ref "CON6") (pin "6") (pinfunction "TRCT2_6") (pintype "bidirectional"))
      (node (ref "CON6") (pin "7") (pinfunction "TRCT4_7") (pintype "bidirectional"))
    )
    (net (code "17") (name "/GBE0_LINK100#") (class "Default")
      (node (ref "R20") (pin "1") (pinfunction "1_1") (pintype "passive"))
    )
    (net (code "18") (name "/GBE0_LINK1000#") (class "Default")
      (node (ref "R21") (pin "1") (pinfunction "1_1") (pintype "passive"))
    )
    (net (code "19") (name "/GBE0_MDI0_N") (class "Default")
      (node (ref "CON6") (pin "10") (pinfunction "TRD1-_10") (pintype "bidirectional"))
    )
    (net (code "20") (name "/GBE0_MDI0_P") (class "Default")
      (node (ref "CON6") (pin "11") (pinfunction "TRD1+_11") (pintype "bidirectional"))
    )
    (net (code "21") (name "/GBE0_MDI1_N") (class "Default")
      (node (ref "CON6") (pin "5") (pinfunction "TRD2-_5") (pintype "bidirectional"))
    )
    (net (code "22") (name "/GBE0_MDI1_P") (class "Default")
      (node (ref "CON6") (pin "4") (pinfunction "TRD2+_4") (pintype "bidirectional"))
    )
    (net (code "23") (name "/GBE0_MDI2_N") (class "Default")
      (node (ref "CON6") (pin "2") (pinfunction "TRD3-_2") (pintype "bidirectional"))
    )
    (net (code "24") (name "/GBE0_MDI2_P") (class "Default")
      (node (ref "CON6") (pin "3") (pinfunction "TRD3+_3") (pintype "bidirectional"))
    )
    (net (code "25") (name "/GBE0_MDI3_N") (class "Default")
      (node (ref "CON6") (pin "9") (pinfunction "TRD4-_9") (pintype "bidirectional"))
    )
    (net (code "26") (name "/GBE0_MDI3_P") (class "Default")
      (node (ref "CON6") (pin "8") (pinfunction "TRD4+_8") (pintype "bidirectional"))
    )
    (net (code "27") (name "/GBE1_ACT#") (class "Default")
      (node (ref "R27") (pin "1") (pinfunction "1_1") (pintype "passive"))
    )
    (net (code "28") (name "/GBE1_CTREF") (class "Default")
      (node (ref "C50") (pin "2") (pinfunction "2_2") (pintype "passive"))
    )
    (net (code "29") (name "/GBE1_LINK100#") (class "Default")
      (node (ref "R30") (pin "1") (pinfunction "1_1") (pintype "passive"))
    )
    (net (code "30") (name "/GBE1_LINK1000#") (class "Default")
      (node (ref "R31") (pin "1") (pinfunction "1_1") (pintype "passive"))
    )
    (net (code "31") (name "/GBE1_MDI0_N") (class "Default")
      (node (ref "C57") (pin "2") (pinfunction "2_2") (pintype "passive"))
      (node (ref "R44") (pin "1") (pinfunction "1_1") (pintype "passive"))
    )
    (net (code "32") (name "/GBE1_MDI0_P") (class "Default")
      (node (ref "C56") (pin "2") (pinfunction "2_2") (pintype "passive"))
      (node (ref "R45") (pin "1") (pinfunction "1_1") (pintype "passive"))
    )
    (net (code "33") (name "/GBE1_MDI1_N") (class "Default")
      (node (ref "C59") (pin "2") (pinfunction "2_2") (pintype "passive"))
      (node (ref "R42") (pin "1") (pinfunction "1_1") (pintype "passive"))
    )
    (net (code "34") (name "/GBE1_MDI1_P") (class "Default")
      (node (ref "C58") (pin "2") (pinfunction "2_2") (pintype "passive"))
      (node (ref "R43") (pin "1") (pinfunction "1_1") (pintype "passive"))
    )
    (net (code "35") (name "/GBE1_MDI2_N") (class "Default")
      (node (ref "C61") (pin "2") (pinfunction "2_2") (pintype "passive"))
      (node (ref "R51") (pin "2") (pinfunction "2_2") (pintype "passive"))
    )
    (net (code "36") (name "/GBE1_MDI2_P") (class "Default")
      (node (ref "C60") (pin "2") (pinfunction "2_2") (pintype "passive"))
      (node (ref "R50") (pin "2") (pinfunction "2_2") (pintype "passive"))
    )
    (net (code "37") (name "/GBE1_MDI3_N") (class "Default")
      (node (ref "C68") (pin "2") (pinfunction "2_2") (pintype "passive"))
      (node (ref "R53") (pin "2") (pinfunction "2_2") (pintype "passive"))
    )
    (net (code "38") (name "/GBE1_MDI3_P") (class "Default")
      (node (ref "C62") (pin "2") (pinfunction "2_2") (pintype "passive"))
      (node (ref "R52") (pin "2") (pinfunction "2_2") (pintype "passive"))
    )
    (net (code "39") (name "/OPMODE_0") (class "Default")
      (node (ref "IC17") (pin "21") (pinfunction "JTAG_CLK/TX_ER_21") (pintype "input"))
      (node (ref "R29") (pin "2") (pinfunction "2_2") (pintype "passive"))
    )
    (net (code "40") (name "/OPMODE_1") (class "Default")
      (node (ref "IC17") (pin "36") (pinfunction "RX_D3_36") (pintype "output"))
      (node (ref "R36") (pin "1") (pinfunction "1_1") (pintype "passive"))
    )
    (net (code "41") (name "/OPMODE_2") (class "Default")
      (node (ref "IC17") (pin "35") (pinfunction "RX_D2_35") (pintype "output"))
      (node (ref "R37") (pin "1") (pinfunction "1_1") (pintype "passive"))
    )
    (net (code "42") (name "/PHY_RSTn") (class "Default")
      (node (ref "IC17") (pin "43") (pinfunction "RESET_N_43") (pintype "input"))
      (node (ref "R22") (pin "1") (pinfunction "1_1") (pintype "passive"))
      (node (ref "R33") (pin "1") (pinfunction "1_1") (pintype "passive"))
      (node (ref "R41") (pin "2") (pinfunction "2_2") (pintype "passive"))
    )
    (net (code "43") (name "/SFPRX_N") (class "Default")
      (node (ref "IC17") (pin "17") (pinfunction "SIN_17") (pintype "input"))
    )
    (net (code "44") (name "/SFPRX_P") (class "Default")
      (node (ref "IC17") (pin "16") (pinfunction "SIP_16") (pintype "input"))
    )
    (net (code "45") (name "/SFPTX_N") (class "Default")
      (node (ref "IC17") (pin "14") (pinfunction "SON_14") (pintype "output"))
    )
    (net (code "46") (name "/SFPTX_P") (class "Default")
      (node (ref "IC17") (pin "15") (pinfunction "SOP_15") (pintype "output"))
    )
    (net (code "47") (name "/SFP_LOS") (class "Default")
      (node (ref "IC17") (pin "24") (pinfunction "JTAG_TDI/SD_24") (pintype "input"))
    )
    (net (code "50") (name "GND") (class "Default")
      (node (ref "C152") (pin "2") (pinfunction "2_2") (pintype "passive"))
      (node (ref "C153") (pin "2") (pinfunction "2_2") (pintype "passive"))
      (node (ref "C154") (pin "1") (pinfunction "1_1") (pintype "passive"))
      (node (ref "C155") (pin "1") (pinfunction "1_1") (pintype "passive"))
      (node (ref "C46") (pin "1") (pinfunction "1_1") (pintype "passive"))
      (node (ref "C47") (pin "1") (pinfunction "1_1") (pintype "passive"))
      (node (ref "C48") (pin "1") (pinfunction "1_1") (pintype "passive"))
      (node (ref "C49") (pin "1") (pinfunction "1_1") (pintype "passive"))
      (node (ref "C50") (pin "1") (pinfunction "1_1") (pintype "passive"))
      (node (ref "C51") (pin "1") (pinfunction "1_1") (pintype "passive"))
      (node (ref "C52") (pin "1") (pinfunction "1_1") (pintype "passive"))
      (node (ref "C53") (pin "1") (pinfunction "1_1") (pintype "passive"))
      (node (ref "C54") (pin "1") (pinfunction "1_1") (pintype "passive"))
      (node (ref "C55") (pin "2") (pinfunction "2_2") (pintype "passive"))
      (node (ref "C63") (pin "1") (pinfunction "1_1") (pintype "passive"))
      (node (ref "C64") (pin "1") (pinfunction "1_1") (pintype "passive"))
      (node (ref "C65") (pin "1") (pinfunction "1_1") (pintype "passive"))
      (node (ref "C66") (pin "1") (pinfunction "1_1") (pintype "passive"))
      (node (ref "C67") (pin "1") (pinfunction "1_1") (pintype "passive"))
      (node (ref "C69") (pin "1") (pinfunction "1_1") (pintype "passive"))
      (node (ref "C70") (pin "1") (pinfunction "1_1") (pintype "passive"))
      (node (ref "C71") (pin "1") (pinfunction "1_1") (pintype "passive"))
      (node (ref "C72") (pin "1") (pinfunction "1_1") (pintype "passive"))
      (node (ref "C73") (pin "1") (pinfunction "1_1") (pintype "passive"))
      (node (ref "C74") (pin "1") (pinfunction "1_1") (pintype "passive"))
      (node (ref "C75") (pin "1") (pinfunction "1_1") (pintype "passive"))
      (node (ref "C76") (pin "1") (pinfunction "1_1") (pintype "passive"))
      (node (ref "C77") (pin "1") (pinfunction "1_1") (pintype "passive"))
      (node (ref "C78") (pin "1") (pinfunction "1_1") (pintype "passive"))
      (node (ref "C79") (pin "1") (pinfunction "1_1") (pintype "passive"))
      (node (ref "C80") (pin "1") (pinfunction "1_1") (pintype "passive"))
      (node (ref "C81") (pin "1") (pinfunction "1_1") (pintype "passive"))
      (node (ref "C82") (pin "1") (pinfunction "1_1") (pintype "passive"))
      (node (ref "C83") (pin "1") (pinfunction "1_1") (pintype "passive"))
      (node (ref "C84") (pin "1") (pinfunction "1_1") (pintype "passive"))
      (node (ref "C85") (pin "1") (pinfunction "1_1") (pintype "passive"))
      (node (ref "C86") (pin "1") (pinfunction "1_1") (pintype "passive"))
      (node (ref "C87") (pin "1") (pinfunction "1_1") (pintype "passive"))
      (node (ref "C88") (pin "1") (pinfunction "1_1") (pintype "passive"))
      (node (ref "C89") (pin "1") (pinfunction "1_1") (pintype "passive"))
      (node (ref "C90") (pin "1") (pinfunction "1_1") (pintype "passive"))
      (node (ref "IC17") (pin "49") (pinfunction "EP_(GND)_49") (pintype "power_in"))
      (node (ref "Q1") (pin "2") (pinfunction "GND_2") (pintype "power_in"))
      (node (ref "Q1") (pin "4") (pinfunction "GND_4") (pintype "power_in"))
      (node (ref "R34") (pin "2") (pinfunction "2_2") (pintype "passive"))
    )
    (net (code "51") (name "Net-(C51-Pad2)") (class "Default")
      (node (ref "C51") (pin "2") (pinfunction "2_2") (pintype "passive"))
      (node (ref "C52") (pin "2") (pinfunction "2_2") (pintype "passive"))
      (node (ref "R22") (pin "2") (pinfunction "2_2") (pintype "passive"))
    )
    (net (code "52") (name "Net-(C55-Pad1)") (class "Default")
      (node (ref "C55") (pin "1") (pinfunction "1_1") (pintype "passive"))
      (node (ref "R42") (pin "2") (pinfunction "2_2") (pintype "passive"))
      (node (ref "R43") (pin "2") (pinfunction "2_2") (pintype "passive"))
      (node (ref "R44") (pin "2") (pinfunction "2_2") (pintype "passive"))
      (node (ref "R45") (pin "2") (pinfunction "2_2") (pintype "passive"))
    )
    (net (code "53") (name "Net-(C78-Pad2)") (class "Default")
      (node (ref "C78") (pin "2") (pinfunction "2_2") (pintype "passive"))
      (node (ref "R50") (pin "1") (pinfunction "1_1") (pintype "passive"))
      (node (ref "R51") (pin "1") (pinfunction "1_1") (pintype "passive"))
      (node (ref "R52") (pin "1") (pinfunction "1_1") (pintype "passive"))
      (node (ref "R53") (pin "1") (pinfunction "1_1") (pintype "passive"))
    )
    (net (code "54") (name "Net-(C152-Pad1)") (class "Default")
      (node (ref "C152") (pin "1") (pinfunction "1_1") (pintype "passive"))
      (node (ref "R11") (pin "2") (pinfunction "2_2") (pintype "passive"))
      (node (ref "R9") (pin "2") (pinfunction "2_2") (pintype "passive"))
    )
    (net (code "55") (name "Net-(C153-Pad1)") (class "Default")
      (node (ref "C153") (pin "1") (pinfunction "1_1") (pintype "passive"))
      (node (ref "R10") (pin "2") (pinfunction "2_2") (pintype "passive"))
      (node (ref "R12") (pin "2") (pinfunction "2_2") (pintype "passive"))
    )
    (net (code "56") (name "Net-(C154-Pad2)") (class "Default")
      (node (ref "C154") (pin "2") (pinfunction "2_2") (pintype "passive"))
      (node (ref "R14") (pin "1") (pinfunction "1_1") (pintype "passive"))
      (node (ref "R15") (pin "1") (pinfunction "1_1") (pintype "passive"))
    )
    (net (code "57") (name "Net-(C155-Pad2)") (class "Default")
      (node (ref "C155") (pin "2") (pinfunction "2_2") (pintype "passive"))
      (node (ref "R16") (pin "1") (pinfunction "1_1") (pintype "passive"))
      (node (ref "R17") (pin "1") (pinfunction "1_1") (pintype "passive"))
    )
    (net (code "58") (name "Net-(CON6-LED1K)") (class "Default")
      (node (ref "CON6") (pin "13") (pinfunction "LED1K_13") (pintype "bidirectional"))
      (node (ref "R19") (pin "2") (pinfunction "2_2") (pintype "passive"))
    )
    (net (code "59") (name "Net-(CON6-LEDG2K)") (class "Default")
      (node (ref "CON6") (pin "17") (pinfunction "LEDG2K_17") (pintype "bidirectional"))
      (node (ref "R21") (pin "2") (pinfunction "2_2") (pintype "passive"))
    )
    (net (code "60") (name "Net-(CON6-LEDO2K)") (class "Default")
      (node (ref "CON6") (pin "15") (pinfunction "LEDO2K_15") (pintype "bidirectional"))
      (node (ref "R20") (pin "2") (pinfunction "2_2") (pintype "passive"))
    )
    (net (code "61") (name "Net-(IC17-INT_N{slash}PWDN_N)") (class "Default")
      (node (ref "IC17") (pin "44") (pinfunction "INT_N/PWDN_N_44") (pintype "bidirectional"))
      (node (ref "R32") (pin "1") (pinfunction "1_1") (pintype "passive"))
    )
    (net (code "62") (name "Net-(IC17-MDC)") (class "Default")
      (node (ref "IC17") (pin "42") (pinfunction "MDC_42") (pintype "input"))
      (node (ref "R25") (pin "2") (pinfunction "2_2") (pintype "passive"))
    )
    (net (code "63") (name "Net-(IC17-MDIO)") (class "Default")
      (node (ref "IC17") (pin "41") (pinfunction "MDIO_41") (pintype "bidirectional"))
      (node (ref "R23") (pin "2") (pinfunction "2_2") (pintype "passive"))
    )
    (net (code "64") (name "Net-(IC17-RBIAS)") (class "Default")
      (node (ref "IC17") (pin "12") (pinfunction "RBIAS_12") (pintype "passive"))
      (node (ref "R34") (pin "1") (pinfunction "1_1") (pintype "passive"))
    )
    (net (code "65") (name "Net-(IC17-XI)") (class "Default")
      (node (ref "C54") (pin "2") (pinfunction "2_2") (pintype "passive"))
      (node (ref "IC17") (pin "20") (pinfunction "XI_20") (pintype "input"))
      (node (ref "Q1") (pin "3") (pinfunction "X_3") (pintype "passive"))
    )
    (net (code "66") (name "Net-(IC17-XO)") (class "Default")
      (node (ref "C53") (pin "2") (pinfunction "2_2") (pintype "passive"))
      (node (ref "IC17") (pin "19") (pinfunction "XO_19") (pintype "output"))
      (node (ref "Q1") (pin "1") (pinfunction "X_1") (pintype "passive"))
    )
    (net (code "67") (name "Net-(LD1-C)") (class "Default")
      (node (ref "LD1") (pin "1") (pinfunction "C_1") (pintype "passive"))
      (node (ref "R30") (pin "2") (pinfunction "2_2") (pintype "passive"))
    )
    (net (code "68") (name "Net-(LD2-C)") (class "Default")
      (node (ref "LD2") (pin "1") (pinfunction "C_1") (pintype "passive"))
      (node (ref "R27") (pin "2") (pinfunction "2_2") (pintype "passive"))
    )
    (net (code "69") (name "Net-(LD3-C)") (class "Default")
      (node (ref "LD3") (pin "1") (pinfunction "C_1") (pintype "passive"))
      (node (ref "R31") (pin "2") (pinfunction "2_2") (pintype "passive"))
    )
    (net (code "70") (name "Net-(LD5-A)") (class "Default")
      (node (ref "LD5") (pin "2") (pinfunction "A_2") (pintype "passive"))
      (node (ref "R46") (pin "1") (pinfunction "1_1") (pintype "passive"))
    )
    (net (code "71") (name "Net-(LD6-A)") (class "Default")
      (node (ref "LD6") (pin "2") (pinfunction "A_2") (pintype "passive"))
      (node (ref "R47") (pin "1") (pinfunction "1_1") (pintype "passive"))
    )
    (net (code "72") (name "Net-(LD7-A)") (class "Default")
      (node (ref "LD7") (pin "2") (pinfunction "A_2") (pintype "passive"))
      (node (ref "R48") (pin "1") (pinfunction "1_1") (pintype "passive"))
    )
    (net (code "73") (name "P1V1") (class "Default")
      (node (ref "C65") (pin "2") (pinfunction "2_2") (pintype "passive"))
      (node (ref "C66") (pin "2") (pinfunction "2_2") (pintype "passive"))
      (node (ref "C67") (pin "2") (pinfunction "2_2") (pintype "passive"))
      (node (ref "C73") (pin "2") (pinfunction "2_2") (pintype "passive"))
      (node (ref "C74") (pin "2") (pinfunction "2_2") (pintype "passive"))
      (node (ref "C75") (pin "2") (pinfunction "2_2") (pintype "passive"))
      (node (ref "C76") (pin "2") (pinfunction "2_2") (pintype "passive"))
      (node (ref "C77") (pin "2") (pinfunction "2_2") (pintype "passive"))
      (node (ref "IC17") (pin "31") (pinfunction "VDD1P1_31") (pintype "power_in"))
      (node (ref "IC17") (pin "39") (pinfunction "VDD1P1_39") (pintype "power_in"))
      (node (ref "IC17") (pin "6") (pinfunction "VDD1P1_6") (pintype "power_in"))
    )
    (net (code "74") (name "P1V8") (class "Default")
      (node (ref "C81") (pin "2") (pinfunction "2_2") (pintype "passive"))
      (node (ref "C82") (pin "2") (pinfunction "2_2") (pintype "passive"))
      (node (ref "C87") (pin "2") (pinfunction "2_2") (pintype "passive"))
      (node (ref "C88") (pin "2") (pinfunction "2_2") (pintype "passive"))
      (node (ref "C89") (pin "2") (pinfunction "2_2") (pintype "passive"))
      (node (ref "C90") (pin "2") (pinfunction "2_2") (pintype "passive"))
      (node (ref "IC17") (pin "13") (pinfunction "VDDA1P8_1_13") (pintype "power_in"))
      (node (ref "IC17") (pin "48") (pinfunction "VDDA1P8_2_48") (pintype "power_in"))
    )
    (net (code "75") (name "P2V5") (class "Default")
      (node (ref "C79") (pin "2") (pinfunction "2_2") (pintype "passive"))
      (node (ref "C80") (pin "2") (pinfunction "2_2") (pintype "passive"))
      (node (ref "C83") (pin "2") (pinfunction "2_2") (pintype "passive"))
      (node (ref "C84") (pin "2") (pinfunction "2_2") (pintype "passive"))
      (node (ref "C85") (pin "2") (pinfunction "2_2") (pintype "passive"))
      (node (ref "C86") (pin "2") (pinfunction "2_2") (pintype "passive"))
      (node (ref "IC17") (pin "3") (pinfunction "VDDA2P5_3") (pintype "power_in"))
      (node (ref "IC17") (pin "9") (pinfunction "VDDA2P5_9") (pintype "power_in"))
    )
    (net (code "76") (name "P3V3") (class "Default")
      (node (ref "C63") (pin "2") (pinfunction "2_2") (pintype "passive"))
      (node (ref "C64") (pin "2") (pinfunction "2_2") (pintype "passive"))
      (node (ref "C69") (pin "2") (pinfunction "2_2") (pintype "passive"))
      (node (ref "C70") (pin "2") (pinfunction "2_2") (pintype "passive"))
      (node (ref "C71") (pin "2") (pinfunction "2_2") (pintype "passive"))
      (node (ref "C72") (pin "2") (pinfunction "2_2") (pintype "passive"))
      (node (ref "CON6") (pin "14") (pinfunction "LED1A_14") (pintype "bidirectional"))
      (node (ref "CON6") (pin "16") (pinfunction "LED2A_16") (pintype "bidirectional"))
      (node (ref "IC17") (pin "18") (pinfunction "VDDIO_18") (pintype "power_in"))
      (node (ref "IC17") (pin "30") (pinfunction "VDDIO_30") (pintype "power_in"))
      (node (ref "LD1") (pin "2") (pinfunction "A_2") (pintype "passive"))
      (node (ref "LD2") (pin "2") (pinfunction "A_2") (pintype "passive"))
      (node (ref "LD3") (pin "2") (pinfunction "A_2") (pintype "passive"))
      (node (ref "R23") (pin "1") (pinfunction "1_1") (pintype "passive"))
      (node (ref "R24") (pin "2") (pinfunction "2_2") (pintype "passive"))
      (node (ref "R25") (pin "1") (pinfunction "1_1") (pintype "passive"))
      (node (ref "R26") (pin "2") (pinfunction "2_2") (pintype "passive"))
      (node (ref "R28") (pin "2") (pinfunction "2_2") (pintype "passive"))
      (node (ref "R29") (pin "1") (pinfunction "1_1") (pintype "passive"))
      (node (ref "R32") (pin "2") (pinfunction "2_2") (pintype "passive"))
      (node (ref "R33") (pin "2") (pinfunction "2_2") (pintype "passive"))
      (node (ref "R36") (pin "2") (pinfunction "2_2") (pintype "passive"))
      (node (ref "R37") (pin "2") (pinfunction "2_2") (pintype "passive"))
      (node (ref "R46") (pin "2") (pinfunction "2_2") (pintype "passive"))
      (node (ref "R47") (pin "2") (pinfunction "2_2") (pintype "passive"))
      (node (ref "R48") (pin "2") (pinfunction "2_2") (pintype "passive"))
    )
    (net (code "77") (name "SHIELD") (class "Default")
      (node (ref "CON6") (pin "18") (pinfunction "SHIELD_18") (pintype "power_in"))
      (node (ref "CON6") (pin "19") (pinfunction "SHIELD_19") (pintype "power_in"))
    )
    (net (code "78") (name "unconnected-(IC17-CLK_OUT-Pad40)") (class "Default")
      (node (ref "IC17") (pin "40") (pinfunction "CLK_OUT_40") (pintype "output+no_connect"))
    )
    (net (code "79") (name "unconnected-(IC17-GTX_CLK{slash}TX_CLK-Pad29)") (class "Default")
      (node (ref "IC17") (pin "29") (pinfunction "GTX_CLK/TX_CLK_29") (pintype "bidirectional+no_connect"))
    )
    (net (code "80") (name "unconnected-(IC17-JTAG_TDO{slash}GPIO_1-Pad22)") (class "Default")
      (node (ref "IC17") (pin "22") (pinfunction "JTAG_TDO/GPIO_1_22") (pintype "output+no_connect"))
    )
    (net (code "81") (name "unconnected-(IC17-JTAG_TMS-Pad23)") (class "Default")
      (node (ref "IC17") (pin "23") (pinfunction "JTAG_TMS_23") (pintype "input+no_connect"))
    )
    (net (code "82") (name "unconnected-(IC17-RX_CLK-Pad32)") (class "Default")
      (node (ref "IC17") (pin "32") (pinfunction "RX_CLK_32") (pintype "output+no_connect"))
    )
    (net (code "83") (name "unconnected-(IC17-RX_CTRL{slash}RX_DV-Pad38)") (class "Default")
      (node (ref "IC17") (pin "38") (pinfunction "RX_CTRL/RX_DV_38") (pintype "output+no_connect"))
    )
    (net (code "84") (name "unconnected-(IC17-RX_D0-Pad33)") (class "Default")
      (node (ref "IC17") (pin "33") (pinfunction "RX_D0_33") (pintype "output+no_connect"))
    )
    (net (code "85") (name "unconnected-(IC17-RX_D1-Pad34)") (class "Default")
      (node (ref "IC17") (pin "34") (pinfunction "RX_D1_34") (pintype "output+no_connect"))
    )
    (net (code "86") (name "unconnected-(IC17-TX_CTRL{slash}TX_EN-Pad37)") (class "Default")
      (node (ref "IC17") (pin "37") (pinfunction "TX_CTRL/TX_EN_37") (pintype "input+no_connect"))
    )
    (net (code "87") (name "unconnected-(IC17-TX_D0-Pad28)") (class "Default")
      (node (ref "IC17") (pin "28") (pinfunction "TX_D0_28") (pintype "input+no_connect"))
    )
    (net (code "88") (name "unconnected-(IC17-TX_D1-Pad27)") (class "Default")
      (node (ref "IC17") (pin "27") (pinfunction "TX_D1_27") (pintype "input+no_connect"))
    )
    (net (code "89") (name "unconnected-(IC17-TX_D2-Pad26)") (class "Default")
      (node (ref "IC17") (pin "26") (pinfunction "TX_D2_26") (pintype "input+no_connect"))
    )
    (net (code "90") (name "unconnected-(IC17-TX_D3-Pad25)") (class "Default")
      (node (ref "IC17") (pin "25") (pinfunction "TX_D3_25") (pintype "input+no_connect"))
    )
  )
)
